# SLT3-PAY-1Q2T_P1.net
KiCad netlist of a schematic drawn in Altium Designer
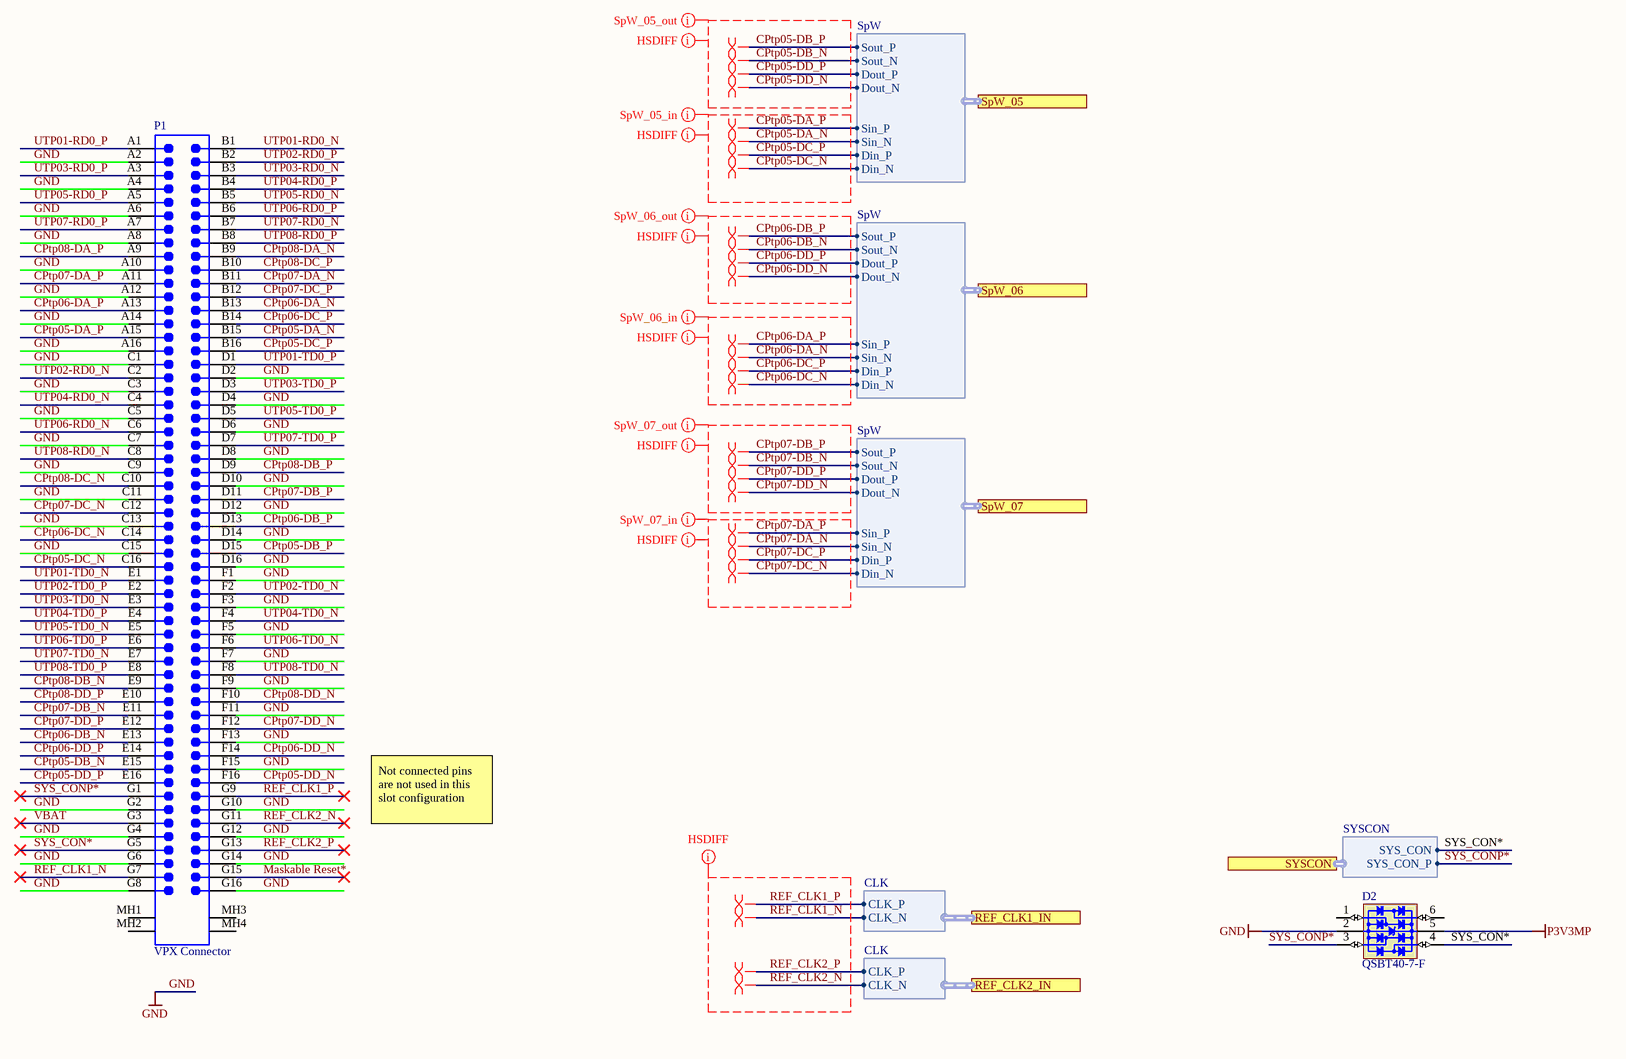
[diagram p0: SLT3-PAY-1Q2T_P1.SchDoc]

(export (version "E")
  (design (tool "Eeschema 10.0.6"))
  (components
    (comp (ref "D2")
      (value "QSBT40-7-F")
      (footprint "SOT65P210X110-6N")
      (libsource (lib "LIBRARY_SCH") (part "D_TVS_QSBT40-7-F"))
    )
    (comp (ref "P1")
      (value "VPX Connector")
      (footprint "BTB1-8-4H112M")
      (description "Ruggedized Board-to-Board Connector, Right Angle, 7-Row, Pitch 1.8mm, 112-Position")
      (fields (field (name "MANUFACTURER") "TE") (field (name "MANUFACTURER PART NUMBER") "2102771-1"))
      (libsource (lib "SVPX") (part "2102771-1"))
    )
  )
  (nets
    (net (code "4") (name "/CPtp05-DA_N") (class "Default")
      (node (ref "P1") (pin "B15") (pinfunction "B15_B15") (pintype "passive"))
    )
    (net (code "5") (name "/CPtp05-DA_P") (class "Default")
      (node (ref "P1") (pin "A15") (pinfunction "A15_A15") (pintype "passive"))
    )
    (net (code "6") (name "/CPtp05-DB_N") (class "Default")
      (node (ref "P1") (pin "E15") (pinfunction "E15_E15") (pintype "passive"))
    )
    (net (code "7") (name "/CPtp05-DB_P") (class "Default")
      (node (ref "P1") (pin "D15") (pinfunction "D15_D15") (pintype "passive"))
    )
    (net (code "8") (name "/CPtp05-DC_N") (class "Default")
      (node (ref "P1") (pin "C16") (pinfunction "C16_C16") (pintype "passive"))
    )
    (net (code "9") (name "/CPtp05-DC_P") (class "Default")
      (node (ref "P1") (pin "B16") (pinfunction "B16_B16") (pintype "passive"))
    )
    (net (code "10") (name "/CPtp05-DD_N") (class "Default")
      (node (ref "P1") (pin "F16") (pinfunction "F16_F16") (pintype "passive"))
    )
    (net (code "11") (name "/CPtp05-DD_P") (class "Default")
      (node (ref "P1") (pin "E16") (pinfunction "E16_E16") (pintype "passive"))
    )
    (net (code "12") (name "/CPtp06-DA_N") (class "Default")
      (node (ref "P1") (pin "B13") (pinfunction "B13_B13") (pintype "passive"))
    )
    (net (code "13") (name "/CPtp06-DA_P") (class "Default")
      (node (ref "P1") (pin "A13") (pinfunction "A13_A13") (pintype "passive"))
    )
    (net (code "14") (name "/CPtp06-DB_N") (class "Default")
      (node (ref "P1") (pin "E13") (pinfunction "E13_E13") (pintype "passive"))
    )
    (net (code "15") (name "/CPtp06-DB_P") (class "Default")
      (node (ref "P1") (pin "D13") (pinfunction "D13_D13") (pintype "passive"))
    )
    (net (code "16") (name "/CPtp06-DC_N") (class "Default")
      (node (ref "P1") (pin "C14") (pinfunction "C14_C14") (pintype "passive"))
    )
    (net (code "17") (name "/CPtp06-DC_P") (class "Default")
      (node (ref "P1") (pin "B14") (pinfunction "B14_B14") (pintype "passive"))
    )
    (net (code "18") (name "/CPtp06-DD_N") (class "Default")
      (node (ref "P1") (pin "F14") (pinfunction "F14_F14") (pintype "passive"))
    )
    (net (code "19") (name "/CPtp06-DD_P") (class "Default")
      (node (ref "P1") (pin "E14") (pinfunction "E14_E14") (pintype "passive"))
    )
    (net (code "20") (name "/CPtp07-DA_N") (class "Default")
      (node (ref "P1") (pin "B11") (pinfunction "B11_B11") (pintype "passive"))
    )
    (net (code "21") (name "/CPtp07-DA_P") (class "Default")
      (node (ref "P1") (pin "A11") (pinfunction "A11_A11") (pintype "passive"))
    )
    (net (code "22") (name "/CPtp07-DB_N") (class "Default")
      (node (ref "P1") (pin "E11") (pinfunction "E11_E11") (pintype "passive"))
    )
    (net (code "23") (name "/CPtp07-DB_P") (class "Default")
      (node (ref "P1") (pin "D11") (pinfunction "D11_D11") (pintype "passive"))
    )
    (net (code "24") (name "/CPtp07-DC_N") (class "Default")
      (node (ref "P1") (pin "C12") (pinfunction "C12_C12") (pintype "passive"))
    )
    (net (code "25") (name "/CPtp07-DC_P") (class "Default")
      (node (ref "P1") (pin "B12") (pinfunction "B12_B12") (pintype "passive"))
    )
    (net (code "26") (name "/CPtp07-DD_N") (class "Default")
      (node (ref "P1") (pin "F12") (pinfunction "F12_F12") (pintype "passive"))
    )
    (net (code "27") (name "/CPtp07-DD_P") (class "Default")
      (node (ref "P1") (pin "E12") (pinfunction "E12_E12") (pintype "passive"))
    )
    (net (code "28") (name "/CPtp08-DA_N") (class "Default")
      (node (ref "P1") (pin "B9") (pinfunction "B9_B9") (pintype "passive"))
    )
    (net (code "29") (name "/CPtp08-DA_P") (class "Default")
      (node (ref "P1") (pin "A9") (pinfunction "A9_A9") (pintype "passive"))
    )
    (net (code "30") (name "/CPtp08-DB_N") (class "Default")
      (node (ref "P1") (pin "E9") (pinfunction "E9_E9") (pintype "passive"))
    )
    (net (code "31") (name "/CPtp08-DB_P") (class "Default")
      (node (ref "P1") (pin "D9") (pinfunction "D9_D9") (pintype "passive"))
    )
    (net (code "32") (name "/CPtp08-DC_N") (class "Default")
      (node (ref "P1") (pin "C10") (pinfunction "C10_C10") (pintype "passive"))
    )
    (net (code "33") (name "/CPtp08-DC_P") (class "Default")
      (node (ref "P1") (pin "B10") (pinfunction "B10_B10") (pintype "passive"))
    )
    (net (code "34") (name "/CPtp08-DD_N") (class "Default")
      (node (ref "P1") (pin "F10") (pinfunction "F10_F10") (pintype "passive"))
    )
    (net (code "35") (name "/CPtp08-DD_P") (class "Default")
      (node (ref "P1") (pin "E10") (pinfunction "E10_E10") (pintype "passive"))
    )
    (net (code "36") (name "/Maskable Reset*") (class "Default")
      (node (ref "P1") (pin "G15") (pinfunction "G15_G15") (pintype "passive+no_connect"))
    )
    (net (code "37") (name "/REF_CLK1_N") (class "Default")
      (node (ref "P1") (pin "G7") (pinfunction "G7_G7") (pintype "passive"))
    )
    (net (code "38") (name "/REF_CLK1_P") (class "Default")
      (node (ref "P1") (pin "G9") (pinfunction "G9_G9") (pintype "passive"))
    )
    (net (code "39") (name "/REF_CLK2_N") (class "Default")
      (node (ref "P1") (pin "G11") (pinfunction "G11_G11") (pintype "passive"))
    )
    (net (code "40") (name "/REF_CLK2_P") (class "Default")
      (node (ref "P1") (pin "G13") (pinfunction "G13_G13") (pintype "passive"))
    )
    (net (code "41") (name "/SYS_CON*") (class "Default")
      (node (ref "D2") (pin "4") (pinfunction "I/O3_4") (pintype "bidirectional"))
      (node (ref "P1") (pin "G5") (pinfunction "G5_G5") (pintype "passive"))
    )
    (net (code "42") (name "/SYS_CONP*") (class "Default")
      (node (ref "D2") (pin "3") (pinfunction "I/O2_3") (pintype "bidirectional"))
      (node (ref "P1") (pin "G1") (pinfunction "G1_G1") (pintype "passive"))
    )
    (net (code "43") (name "/UTP01-RD0_N") (class "Default")
      (node (ref "P1") (pin "B1") (pinfunction "B1_B1") (pintype "passive"))
    )
    (net (code "44") (name "/UTP01-RD0_P") (class "Default")
      (node (ref "P1") (pin "A1") (pinfunction "A1_A1") (pintype "passive"))
    )
    (net (code "45") (name "/UTP01-TD0_N") (class "Default")
      (node (ref "P1") (pin "E1") (pinfunction "E1_E1") (pintype "passive"))
    )
    (net (code "46") (name "/UTP01-TD0_P") (class "Default")
      (node (ref "P1") (pin "D1") (pinfunction "D1_D1") (pintype "passive"))
    )
    (net (code "47") (name "/UTP02-RD0_N") (class "Default")
      (node (ref "P1") (pin "C2") (pinfunction "C2_C2") (pintype "passive"))
    )
    (net (code "48") (name "/UTP02-RD0_P") (class "Default")
      (node (ref "P1") (pin "B2") (pinfunction "B2_B2") (pintype "passive"))
    )
    (net (code "49") (name "/UTP02-TD0_N") (class "Default")
      (node (ref "P1") (pin "F2") (pinfunction "F2_F2") (pintype "passive"))
    )
    (net (code "50") (name "/UTP02-TD0_P") (class "Default")
      (node (ref "P1") (pin "E2") (pinfunction "E2_E2") (pintype "passive"))
    )
    (net (code "51") (name "/UTP03-RD0_N") (class "Default")
      (node (ref "P1") (pin "B3") (pinfunction "B3_B3") (pintype "passive"))
    )
    (net (code "52") (name "/UTP03-RD0_P") (class "Default")
      (node (ref "P1") (pin "A3") (pinfunction "A3_A3") (pintype "passive"))
    )
    (net (code "53") (name "/UTP03-TD0_N") (class "Default")
      (node (ref "P1") (pin "E3") (pinfunction "E3_E3") (pintype "passive"))
    )
    (net (code "54") (name "/UTP03-TD0_P") (class "Default")
      (node (ref "P1") (pin "D3") (pinfunction "D3_D3") (pintype "passive"))
    )
    (net (code "55") (name "/UTP04-RD0_N") (class "Default")
      (node (ref "P1") (pin "C4") (pinfunction "C4_C4") (pintype "passive"))
    )
    (net (code "56") (name "/UTP04-RD0_P") (class "Default")
      (node (ref "P1") (pin "B4") (pinfunction "B4_B4") (pintype "passive"))
    )
    (net (code "57") (name "/UTP04-TD0_N") (class "Default")
      (node (ref "P1") (pin "F4") (pinfunction "F4_F4") (pintype "passive"))
    )
    (net (code "58") (name "/UTP04-TD0_P") (class "Default")
      (node (ref "P1") (pin "E4") (pinfunction "E4_E4") (pintype "passive"))
    )
    (net (code "59") (name "/UTP05-RD0_N") (class "Default")
      (node (ref "P1") (pin "B5") (pinfunction "B5_B5") (pintype "passive"))
    )
    (net (code "60") (name "/UTP05-RD0_P") (class "Default")
      (node (ref "P1") (pin "A5") (pinfunction "A5_A5") (pintype "passive"))
    )
    (net (code "61") (name "/UTP05-TD0_N") (class "Default")
      (node (ref "P1") (pin "E5") (pinfunction "E5_E5") (pintype "passive"))
    )
    (net (code "62") (name "/UTP05-TD0_P") (class "Default")
      (node (ref "P1") (pin "D5") (pinfunction "D5_D5") (pintype "passive"))
    )
    (net (code "63") (name "/UTP06-RD0_N") (class "Default")
      (node (ref "P1") (pin "C6") (pinfunction "C6_C6") (pintype "passive"))
    )
    (net (code "64") (name "/UTP06-RD0_P") (class "Default")
      (node (ref "P1") (pin "B6") (pinfunction "B6_B6") (pintype "passive"))
    )
    (net (code "65") (name "/UTP06-TD0_N") (class "Default")
      (node (ref "P1") (pin "F6") (pinfunction "F6_F6") (pintype "passive"))
    )
    (net (code "66") (name "/UTP06-TD0_P") (class "Default")
      (node (ref "P1") (pin "E6") (pinfunction "E6_E6") (pintype "passive"))
    )
    (net (code "67") (name "/UTP07-RD0_N") (class "Default")
      (node (ref "P1") (pin "B7") (pinfunction "B7_B7") (pintype "passive"))
    )
    (net (code "68") (name "/UTP07-RD0_P") (class "Default")
      (node (ref "P1") (pin "A7") (pinfunction "A7_A7") (pintype "passive"))
    )
    (net (code "69") (name "/UTP07-TD0_N") (class "Default")
      (node (ref "P1") (pin "E7") (pinfunction "E7_E7") (pintype "passive"))
    )
    (net (code "70") (name "/UTP07-TD0_P") (class "Default")
      (node (ref "P1") (pin "D7") (pinfunction "D7_D7") (pintype "passive"))
    )
    (net (code "71") (name "/UTP08-RD0_N") (class "Default")
      (node (ref "P1") (pin "C8") (pinfunction "C8_C8") (pintype "passive"))
    )
    (net (code "72") (name "/UTP08-RD0_P") (class "Default")
      (node (ref "P1") (pin "B8") (pinfunction "B8_B8") (pintype "passive"))
    )
    (net (code "73") (name "/UTP08-TD0_N") (class "Default")
      (node (ref "P1") (pin "F8") (pinfunction "F8_F8") (pintype "passive"))
    )
    (net (code "74") (name "/UTP08-TD0_P") (class "Default")
      (node (ref "P1") (pin "E8") (pinfunction "E8_E8") (pintype "passive"))
    )
    (net (code "75") (name "/VBAT") (class "Default")
      (node (ref "P1") (pin "G3") (pinfunction "G3_G3") (pintype "passive+no_connect"))
    )
    (net (code "79") (name "GND") (class "Default")
      (node (ref "D2") (pin "2") (pinfunction "GND_2") (pintype "power_in"))
      (node (ref "P1") (pin "A10") (pinfunction "A10_A10") (pintype "passive"))
      (node (ref "P1") (pin "A12") (pinfunction "A12_A12") (pintype "passive"))
      (node (ref "P1") (pin "A14") (pinfunction "A14_A14") (pintype "passive"))
      (node (ref "P1") (pin "A16") (pinfunction "A16_A16") (pintype "passive"))
      (node (ref "P1") (pin "A2") (pinfunction "A2_A2") (pintype "passive"))
      (node (ref "P1") (pin "A4") (pinfunction "A4_A4") (pintype "passive"))
      (node (ref "P1") (pin "A6") (pinfunction "A6_A6") (pintype "passive"))
      (node (ref "P1") (pin "A8") (pinfunction "A8_A8") (pintype "passive"))
      (node (ref "P1") (pin "C1") (pinfunction "C1_C1") (pintype "passive"))
      (node (ref "P1") (pin "C11") (pinfunction "C11_C11") (pintype "passive"))
      (node (ref "P1") (pin "C13") (pinfunction "C13_C13") (pintype "passive"))
      (node (ref "P1") (pin "C15") (pinfunction "C15_C15") (pintype "passive"))
      (node (ref "P1") (pin "C3") (pinfunction "C3_C3") (pintype "passive"))
      (node (ref "P1") (pin "C5") (pinfunction "C5_C5") (pintype "passive"))
      (node (ref "P1") (pin "C7") (pinfunction "C7_C7") (pintype "passive"))
      (node (ref "P1") (pin "C9") (pinfunction "C9_C9") (pintype "passive"))
      (node (ref "P1") (pin "D10") (pinfunction "D10_D10") (pintype "passive"))
      (node (ref "P1") (pin "D12") (pinfunction "D12_D12") (pintype "passive"))
      (node (ref "P1") (pin "D14") (pinfunction "D14_D14") (pintype "passive"))
      (node (ref "P1") (pin "D16") (pinfunction "D16_D16") (pintype "passive"))
      (node (ref "P1") (pin "D2") (pinfunction "D2_D2") (pintype "passive"))
      (node (ref "P1") (pin "D4") (pinfunction "D4_D4") (pintype "passive"))
      (node (ref "P1") (pin "D6") (pinfunction "D6_D6") (pintype "passive"))
      (node (ref "P1") (pin "D8") (pinfunction "D8_D8") (pintype "passive"))
      (node (ref "P1") (pin "F1") (pinfunction "F1_F1") (pintype "passive"))
      (node (ref "P1") (pin "F11") (pinfunction "F11_F11") (pintype "passive"))
      (node (ref "P1") (pin "F13") (pinfunction "F13_F13") (pintype "passive"))
      (node (ref "P1") (pin "F15") (pinfunction "F15_F15") (pintype "passive"))
      (node (ref "P1") (pin "F3") (pinfunction "F3_F3") (pintype "passive"))
      (node (ref "P1") (pin "F5") (pinfunction "F5_F5") (pintype "passive"))
      (node (ref "P1") (pin "F7") (pinfunction "F7_F7") (pintype "passive"))
      (node (ref "P1") (pin "F9") (pinfunction "F9_F9") (pintype "passive"))
      (node (ref "P1") (pin "G10") (pinfunction "G10_G10") (pintype "passive"))
      (node (ref "P1") (pin "G12") (pinfunction "G12_G12") (pintype "passive"))
      (node (ref "P1") (pin "G14") (pinfunction "G14_G14") (pintype "passive"))
      (node (ref "P1") (pin "G16") (pinfunction "G16_G16") (pintype "passive"))
      (node (ref "P1") (pin "G2") (pinfunction "G2_G2") (pintype "passive"))
      (node (ref "P1") (pin "G4") (pinfunction "G4_G4") (pintype "passive"))
      (node (ref "P1") (pin "G6") (pinfunction "G6_G6") (pintype "passive"))
      (node (ref "P1") (pin "G8") (pinfunction "G8_G8") (pintype "passive"))
    )
    (net (code "80") (name "P3V3MP") (class "Default")
      (node (ref "D2") (pin "5") (pinfunction "VBUS_5") (pintype "power_in"))
    )
    (net (code "81") (name "unconnected-(D2-I{slash}O1-Pad1)") (class "Default")
      (node (ref "D2") (pin "1") (pinfunction "I/O1_1") (pintype "bidirectional"))
    )
    (net (code "82") (name "unconnected-(D2-I{slash}O4-Pad6)") (class "Default")
      (node (ref "D2") (pin "6") (pinfunction "I/O4_6") (pintype "bidirectional"))
    )
    (net (code "83") (name "unconnected-(P1-PadMH1)") (class "Default")
      (node (ref "P1") (pin "MH1") (pinfunction "MH1_MH1") (pintype "passive"))
    )
    (net (code "84") (name "unconnected-(P1-PadMH2)") (class "Default")
      (node (ref "P1") (pin "MH2") (pinfunction "MH2_MH2") (pintype "passive"))
    )
    (net (code "85") (name "unconnected-(P1-PadMH3)") (class "Default")
      (node (ref "P1") (pin "MH3") (pinfunction "MH3_MH3") (pintype "passive"))
    )
    (net (code "86") (name "unconnected-(P1-PadMH4)") (class "Default")
      (node (ref "P1") (pin "MH4") (pinfunction "MH4_MH4") (pintype "passive"))
    )
  )
)
